# TSAL_2016.net
KiCad netlist of a schematic drawn in EAGLE
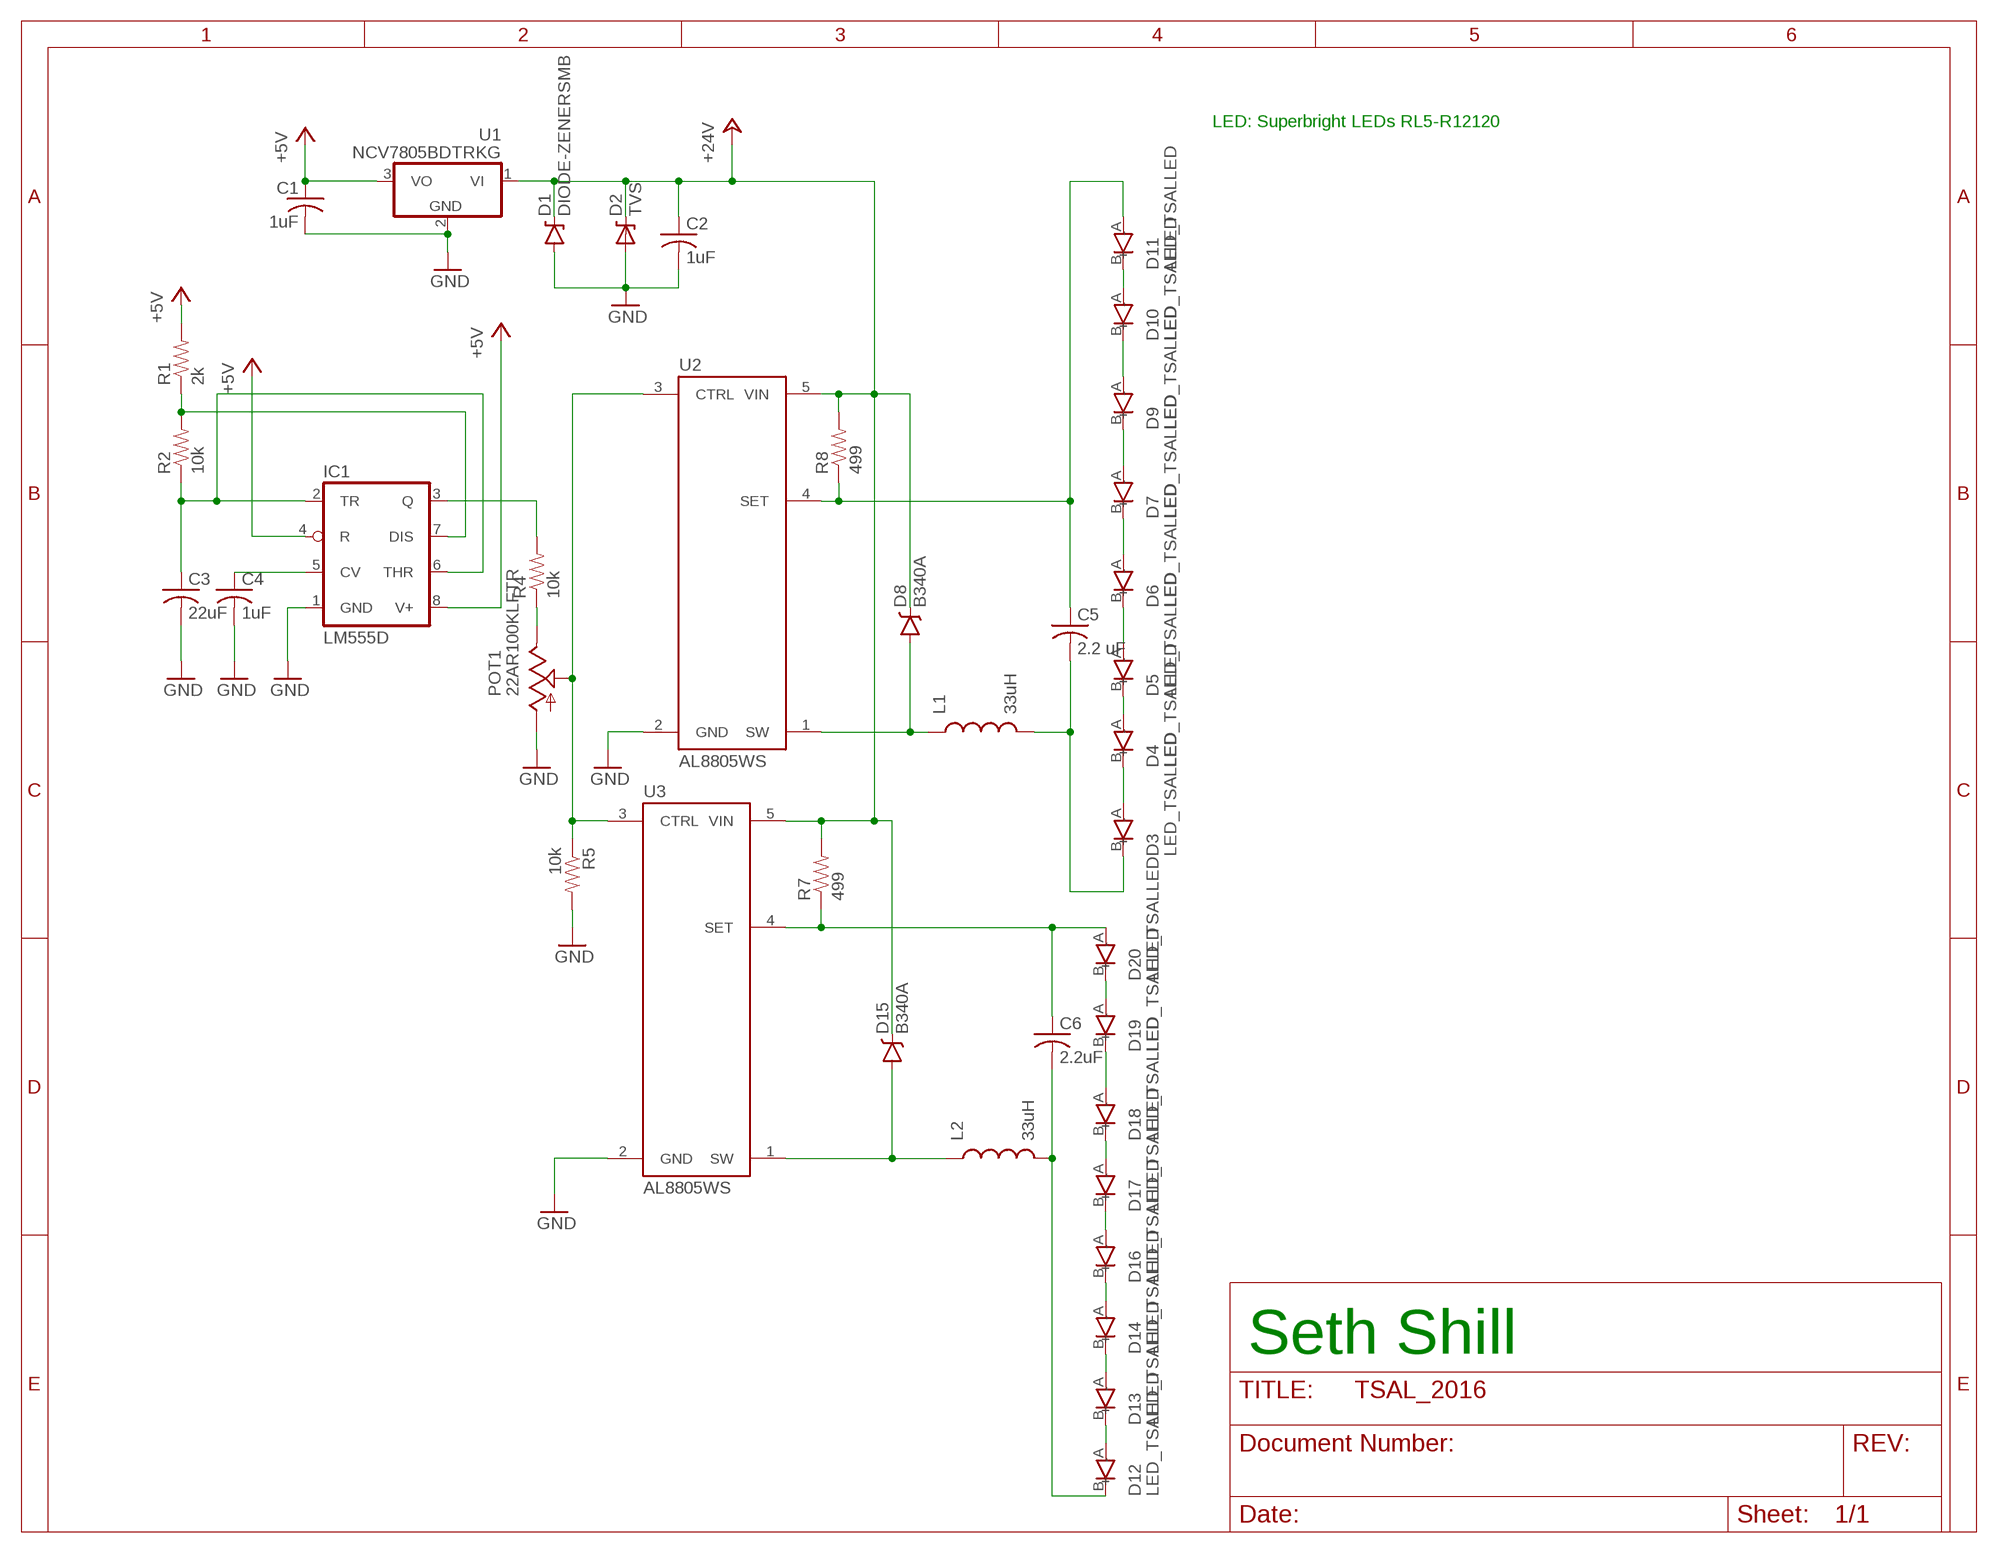
[diagram p0: schematic, sheet 1]

(export (version "E")
  (design (tool "Eeschema 10.0.6"))
  (components
    (comp (ref "C1")
      (value "1uF")
      (footprint "eagle-import:0805@1")
      (fields (field (name "PARTNO") "UMK212F105ZG-T"))
      (libsource (lib "eagle-import") (part "CAP_1UF_50V_0805"))
    )
    (comp (ref "C2")
      (value "1uF")
      (footprint "eagle-import:0805@1")
      (fields (field (name "PARTNO") "UMK212F105ZG-T"))
      (libsource (lib "eagle-import") (part "CAP_1UF_50V_0805"))
    )
    (comp (ref "C3")
      (value "22uF")
      (footprint "eagle-import:0805@1")
      (fields (field (name "PARTNO") "CL21A226MQCLQNC"))
      (libsource (lib "eagle-import") (part "CAP_22UF_6.3V_0805"))
    )
    (comp (ref "C4")
      (value "1uF")
      (footprint "eagle-import:0805@1")
      (fields (field (name "PARTNO") "UMK212F105ZG-T"))
      (libsource (lib "eagle-import") (part "CAP_1UF_50V_0805"))
    )
    (comp (ref "C5")
      (value "2.2 uF")
      (footprint "eagle-import:0603@1")
      (fields (field (name "PARTNO") "EMK107F225ZA-T"))
      (libsource (lib "eagle-import") (part "CAP_2.2UF_16V_0603"))
    )
    (comp (ref "C6")
      (value "2.2uF")
      (footprint "eagle-import:0603@1")
      (fields (field (name "PARTNO") "EMK107F225ZA-T"))
      (libsource (lib "eagle-import") (part "CAP_2.2UF_16V_0603"))
    )
    (comp (ref "D1")
      (value "DIODE-ZENERSMB")
      (footprint "eagle-import:SMB-DIODE")
      (libsource (lib "eagle-import") (part "DIODE-ZENERSMB"))
    )
    (comp (ref "D2")
      (value "TVS")
      (footprint "eagle-import:DO-214AC")
      (libsource (lib "eagle-import") (part "TVS"))
    )
    (comp (ref "D3")
      (value "LED_TSALLED")
      (footprint "eagle-import:LED_TSAL")
      (libsource (lib "eagle-import") (part "LED_TSALLED"))
    )
    (comp (ref "D4")
      (value "LED_TSALLED")
      (footprint "eagle-import:LED_TSAL")
      (libsource (lib "eagle-import") (part "LED_TSALLED"))
    )
    (comp (ref "D5")
      (value "LED_TSALLED")
      (footprint "eagle-import:LED_TSAL")
      (libsource (lib "eagle-import") (part "LED_TSALLED"))
    )
    (comp (ref "D6")
      (value "LED_TSALLED")
      (footprint "eagle-import:LED_TSAL")
      (libsource (lib "eagle-import") (part "LED_TSALLED"))
    )
    (comp (ref "D7")
      (value "LED_TSALLED")
      (footprint "eagle-import:LED_TSAL")
      (libsource (lib "eagle-import") (part "LED_TSALLED"))
    )
    (comp (ref "D8")
      (value "B340A")
      (footprint "eagle-import:SMA-DIODE")
      (libsource (lib "eagle-import") (part "DIODE-SCHOTTKY-B340A"))
    )
    (comp (ref "D9")
      (value "LED_TSALLED")
      (footprint "eagle-import:LED_TSAL")
      (libsource (lib "eagle-import") (part "LED_TSALLED"))
    )
    (comp (ref "D10")
      (value "LED_TSALLED")
      (footprint "eagle-import:LED_TSAL")
      (libsource (lib "eagle-import") (part "LED_TSALLED"))
    )
    (comp (ref "D11")
      (value "LED_TSALLED")
      (footprint "eagle-import:LED_TSAL")
      (libsource (lib "eagle-import") (part "LED_TSALLED"))
    )
    (comp (ref "D12")
      (value "LED_TSALLED")
      (footprint "eagle-import:LED_TSAL")
      (libsource (lib "eagle-import") (part "LED_TSALLED"))
    )
    (comp (ref "D13")
      (value "LED_TSALLED")
      (footprint "eagle-import:LED_TSAL")
      (libsource (lib "eagle-import") (part "LED_TSALLED"))
    )
    (comp (ref "D14")
      (value "LED_TSALLED")
      (footprint "eagle-import:LED_TSAL")
      (libsource (lib "eagle-import") (part "LED_TSALLED"))
    )
    (comp (ref "D15")
      (value "B340A")
      (footprint "eagle-import:SMA-DIODE")
      (libsource (lib "eagle-import") (part "DIODE-SCHOTTKY-B340A"))
    )
    (comp (ref "D16")
      (value "LED_TSALLED")
      (footprint "eagle-import:LED_TSAL")
      (libsource (lib "eagle-import") (part "LED_TSALLED"))
    )
    (comp (ref "D17")
      (value "LED_TSALLED")
      (footprint "eagle-import:LED_TSAL")
      (libsource (lib "eagle-import") (part "LED_TSALLED"))
    )
    (comp (ref "D18")
      (value "LED_TSALLED")
      (footprint "eagle-import:LED_TSAL")
      (libsource (lib "eagle-import") (part "LED_TSALLED"))
    )
    (comp (ref "D19")
      (value "LED_TSALLED")
      (footprint "eagle-import:LED_TSAL")
      (libsource (lib "eagle-import") (part "LED_TSALLED"))
    )
    (comp (ref "D20")
      (value "LED_TSALLED")
      (footprint "eagle-import:LED_TSAL")
      (libsource (lib "eagle-import") (part "LED_TSALLED"))
    )
    (comp (ref "IC1")
      (value "LM555D")
      (footprint "eagle-import:SO08")
      (libsource (lib "eagle-import") (part "555DLM"))
    )
    (comp (ref "L1")
      (value "33uH")
      (footprint "eagle-import:1007")
      (fields (field (name "PARTNO") "CB2518T330K"))
      (libsource (lib "eagle-import") (part "INDUCTOR1007"))
    )
    (comp (ref "L2")
      (value "33uH")
      (footprint "eagle-import:1007")
      (fields (field (name "PARTNO") "CB2518T330K"))
      (libsource (lib "eagle-import") (part "INDUCTOR1007"))
    )
    (comp (ref "POT1")
      (value "22AR100KLFTR")
      (footprint "eagle-import:22AR100KLFTR")
      (libsource (lib "eagle-import") (part "22AR100KLFTR"))
    )
    (comp (ref "R1")
      (value "2k")
      (footprint "eagle-import:0805@1")
      (fields (field (name "PARTNO") "RC0805FR-072KL"))
      (libsource (lib "eagle-import") (part "RES_2K_1%_0805"))
    )
    (comp (ref "R2")
      (value "10k")
      (footprint "eagle-import:0805@1")
      (fields (field (name "PARTNO") "RC0805FR-0710KL"))
      (libsource (lib "eagle-import") (part "RES_10K_1%_0805"))
    )
    (comp (ref "R4")
      (value "10k")
      (footprint "eagle-import:0805@1")
      (fields (field (name "PARTNO") "RC0805FR-0710KL"))
      (libsource (lib "eagle-import") (part "RES_10K_1%_0805"))
    )
    (comp (ref "R5")
      (value "10k")
      (footprint "eagle-import:0805@1")
      (fields (field (name "PARTNO") "RC0805FR-0710KL"))
      (libsource (lib "eagle-import") (part "RES_10K_1%_0805"))
    )
    (comp (ref "R7")
      (value "499")
      (footprint "eagle-import:0603@1")
      (fields (field (name "PARTNO") "RC0603FR-07499RL"))
      (libsource (lib "eagle-import") (part "RES_499_1%"))
    )
    (comp (ref "R8")
      (value "499")
      (footprint "eagle-import:0603@1")
      (fields (field (name "PARTNO") "RC0603FR-07499RL"))
      (libsource (lib "eagle-import") (part "RES_499_1%"))
    )
    (comp (ref "U1")
      (value "NCV7805BDTRKG")
      (footprint "eagle-import:DPAK")
      (libsource (lib "eagle-import") (part "NCV7805BDTRKG"))
    )
    (comp (ref "U2")
      (value "AL8805WS")
      (footprint "eagle-import:SOT23-5")
      (libsource (lib "eagle-import") (part "AL8805"))
    )
    (comp (ref "U3")
      (value "AL8805WS")
      (footprint "eagle-import:SOT23-5")
      (libsource (lib "eagle-import") (part "AL8805"))
    )
  )
  (nets
    (net (code "1") (name "+5V") (class "Default")
      (node (ref "C1") (pin "1") (pinfunction "+_1") (pintype "passive"))
      (node (ref "IC1") (pin "4") (pinfunction "R_4") (pintype "input"))
      (node (ref "IC1") (pin "8") (pinfunction "V+_8") (pintype "power_in"))
      (node (ref "R1") (pin "2") (pinfunction "2_2") (pintype "passive"))
      (node (ref "U1") (pin "3") (pinfunction "VO_3") (pintype "passive"))
    )
    (net (code "2") (name "+24V") (class "Default")
      (node (ref "C2") (pin "1") (pinfunction "+_1") (pintype "passive"))
      (node (ref "D1") (pin "C") (pinfunction "C_C") (pintype "passive"))
      (node (ref "D15") (pin "C") (pinfunction "C_C") (pintype "passive"))
      (node (ref "D2") (pin "C") (pinfunction "C_C") (pintype "passive"))
      (node (ref "D8") (pin "C") (pinfunction "C_C") (pintype "passive"))
      (node (ref "R7") (pin "2") (pinfunction "2_2") (pintype "passive"))
      (node (ref "R8") (pin "2") (pinfunction "2_2") (pintype "passive"))
      (node (ref "U1") (pin "1") (pinfunction "VI_1") (pintype "input"))
      (node (ref "U2") (pin "5") (pinfunction "VIN_5") (pintype "bidirectional"))
      (node (ref "U3") (pin "5") (pinfunction "VIN_5") (pintype "bidirectional"))
    )
    (net (code "3") (name "GND") (class "Default")
      (node (ref "C1") (pin "2") (pinfunction "-_2") (pintype "passive"))
      (node (ref "C2") (pin "2") (pinfunction "-_2") (pintype "passive"))
      (node (ref "C3") (pin "2") (pinfunction "-_2") (pintype "passive"))
      (node (ref "C4") (pin "2") (pinfunction "-_2") (pintype "passive"))
      (node (ref "D1") (pin "A") (pinfunction "A_A") (pintype "passive"))
      (node (ref "D2") (pin "A") (pinfunction "A_A") (pintype "passive"))
      (node (ref "IC1") (pin "1") (pinfunction "GND_1") (pintype "power_in"))
      (node (ref "POT1") (pin "3") (pinfunction "CW_3") (pintype "passive"))
      (node (ref "R5") (pin "2") (pinfunction "2_2") (pintype "passive"))
      (node (ref "U1") (pin "2") (pinfunction "GND_2") (pintype "passive"))
      (node (ref "U2") (pin "2") (pinfunction "GND_2") (pintype "bidirectional"))
      (node (ref "U3") (pin "2") (pinfunction "GND_2") (pintype "bidirectional"))
    )
    (net (code "4") (name "Net-(C3-+)") (class "Default")
      (node (ref "C3") (pin "1") (pinfunction "+_1") (pintype "passive"))
      (node (ref "IC1") (pin "2") (pinfunction "TR_2") (pintype "input"))
      (node (ref "IC1") (pin "6") (pinfunction "THR_6") (pintype "input"))
      (node (ref "R2") (pin "1") (pinfunction "1_1") (pintype "passive"))
    )
    (net (code "5") (name "Net-(C4-+)") (class "Default")
      (node (ref "C4") (pin "1") (pinfunction "+_1") (pintype "passive"))
      (node (ref "IC1") (pin "5") (pinfunction "CV_5") (pintype "input"))
    )
    (net (code "6") (name "Net-(C5-+)") (class "Default")
      (node (ref "C5") (pin "1") (pinfunction "+_1") (pintype "passive"))
      (node (ref "D11") (pin "A") (pinfunction "+_A") (pintype "bidirectional"))
      (node (ref "R8") (pin "1") (pinfunction "1_1") (pintype "passive"))
      (node (ref "U2") (pin "4") (pinfunction "SET_4") (pintype "bidirectional"))
    )
    (net (code "7") (name "Net-(C5--)") (class "Default")
      (node (ref "C5") (pin "2") (pinfunction "-_2") (pintype "passive"))
      (node (ref "D3") (pin "B") (pinfunction "-_B") (pintype "bidirectional"))
      (node (ref "L1") (pin "2") (pinfunction "2_2") (pintype "passive"))
    )
    (net (code "8") (name "Net-(C6-+)") (class "Default")
      (node (ref "C6") (pin "1") (pinfunction "+_1") (pintype "passive"))
      (node (ref "D20") (pin "A") (pinfunction "+_A") (pintype "bidirectional"))
      (node (ref "R7") (pin "1") (pinfunction "1_1") (pintype "passive"))
      (node (ref "U3") (pin "4") (pinfunction "SET_4") (pintype "bidirectional"))
    )
    (net (code "9") (name "Net-(C6--)") (class "Default")
      (node (ref "C6") (pin "2") (pinfunction "-_2") (pintype "passive"))
      (node (ref "D12") (pin "B") (pinfunction "-_B") (pintype "bidirectional"))
      (node (ref "L2") (pin "2") (pinfunction "2_2") (pintype "passive"))
    )
    (net (code "10") (name "Net-(D3-+)") (class "Default")
      (node (ref "D3") (pin "A") (pinfunction "+_A") (pintype "bidirectional"))
      (node (ref "D4") (pin "B") (pinfunction "-_B") (pintype "bidirectional"))
    )
    (net (code "11") (name "Net-(D4-+)") (class "Default")
      (node (ref "D4") (pin "A") (pinfunction "+_A") (pintype "bidirectional"))
      (node (ref "D5") (pin "B") (pinfunction "-_B") (pintype "bidirectional"))
    )
    (net (code "12") (name "Net-(D5-+)") (class "Default")
      (node (ref "D5") (pin "A") (pinfunction "+_A") (pintype "bidirectional"))
      (node (ref "D6") (pin "B") (pinfunction "-_B") (pintype "bidirectional"))
    )
    (net (code "13") (name "Net-(D6-+)") (class "Default")
      (node (ref "D6") (pin "A") (pinfunction "+_A") (pintype "bidirectional"))
      (node (ref "D7") (pin "B") (pinfunction "-_B") (pintype "bidirectional"))
    )
    (net (code "14") (name "Net-(D7-+)") (class "Default")
      (node (ref "D7") (pin "A") (pinfunction "+_A") (pintype "bidirectional"))
      (node (ref "D9") (pin "B") (pinfunction "-_B") (pintype "bidirectional"))
    )
    (net (code "15") (name "Net-(D10-+)") (class "Default")
      (node (ref "D10") (pin "A") (pinfunction "+_A") (pintype "bidirectional"))
      (node (ref "D11") (pin "B") (pinfunction "-_B") (pintype "bidirectional"))
    )
    (net (code "16") (name "Net-(D10--)") (class "Default")
      (node (ref "D10") (pin "B") (pinfunction "-_B") (pintype "bidirectional"))
      (node (ref "D9") (pin "A") (pinfunction "+_A") (pintype "bidirectional"))
    )
    (net (code "17") (name "Net-(D12-+)") (class "Default")
      (node (ref "D12") (pin "A") (pinfunction "+_A") (pintype "bidirectional"))
      (node (ref "D13") (pin "B") (pinfunction "-_B") (pintype "bidirectional"))
    )
    (net (code "18") (name "Net-(D13-+)") (class "Default")
      (node (ref "D13") (pin "A") (pinfunction "+_A") (pintype "bidirectional"))
      (node (ref "D14") (pin "B") (pinfunction "-_B") (pintype "bidirectional"))
    )
    (net (code "19") (name "Net-(D14-+)") (class "Default")
      (node (ref "D14") (pin "A") (pinfunction "+_A") (pintype "bidirectional"))
      (node (ref "D16") (pin "B") (pinfunction "-_B") (pintype "bidirectional"))
    )
    (net (code "20") (name "Net-(D16-+)") (class "Default")
      (node (ref "D16") (pin "A") (pinfunction "+_A") (pintype "bidirectional"))
      (node (ref "D17") (pin "B") (pinfunction "-_B") (pintype "bidirectional"))
    )
    (net (code "21") (name "Net-(D17-+)") (class "Default")
      (node (ref "D17") (pin "A") (pinfunction "+_A") (pintype "bidirectional"))
      (node (ref "D18") (pin "B") (pinfunction "-_B") (pintype "bidirectional"))
    )
    (net (code "22") (name "Net-(D18-+)") (class "Default")
      (node (ref "D18") (pin "A") (pinfunction "+_A") (pintype "bidirectional"))
      (node (ref "D19") (pin "B") (pinfunction "-_B") (pintype "bidirectional"))
    )
    (net (code "23") (name "Net-(D19-+)") (class "Default")
      (node (ref "D19") (pin "A") (pinfunction "+_A") (pintype "bidirectional"))
      (node (ref "D20") (pin "B") (pinfunction "-_B") (pintype "bidirectional"))
    )
    (net (code "24") (name "Net-(IC1-DIS)") (class "Default")
      (node (ref "IC1") (pin "7") (pinfunction "DIS_7") (pintype "input"))
      (node (ref "R1") (pin "1") (pinfunction "1_1") (pintype "passive"))
      (node (ref "R2") (pin "2") (pinfunction "2_2") (pintype "passive"))
    )
    (net (code "25") (name "Net-(IC1-Q)") (class "Default")
      (node (ref "IC1") (pin "3") (pinfunction "Q_3") (pintype "output"))
      (node (ref "R4") (pin "2") (pinfunction "2_2") (pintype "passive"))
    )
    (net (code "26") (name "Net-(POT1-CCW)") (class "Default")
      (node (ref "POT1") (pin "1") (pinfunction "CCW_1") (pintype "passive"))
      (node (ref "R4") (pin "1") (pinfunction "1_1") (pintype "passive"))
    )
    (net (code "27") (name "Net-(POT1-W)") (class "Default")
      (node (ref "POT1") (pin "2") (pinfunction "W_2") (pintype "passive"))
      (node (ref "R5") (pin "1") (pinfunction "1_1") (pintype "passive"))
      (node (ref "U2") (pin "3") (pinfunction "CTRL_3") (pintype "bidirectional"))
      (node (ref "U3") (pin "3") (pinfunction "CTRL_3") (pintype "bidirectional"))
    )
    (net (code "28") (name "Net-(U2-SW)") (class "Default")
      (node (ref "D8") (pin "A") (pinfunction "A_A") (pintype "passive"))
      (node (ref "L1") (pin "1") (pinfunction "1_1") (pintype "passive"))
      (node (ref "U2") (pin "1") (pinfunction "SW_1") (pintype "bidirectional"))
    )
    (net (code "29") (name "Net-(U3-SW)") (class "Default")
      (node (ref "D15") (pin "A") (pinfunction "A_A") (pintype "passive"))
      (node (ref "L2") (pin "1") (pinfunction "1_1") (pintype "passive"))
      (node (ref "U3") (pin "1") (pinfunction "SW_1") (pintype "bidirectional"))
    )
  )
)
